# MFX_LEDs.net
KiCad netlist of a schematic drawn in Altium Designer
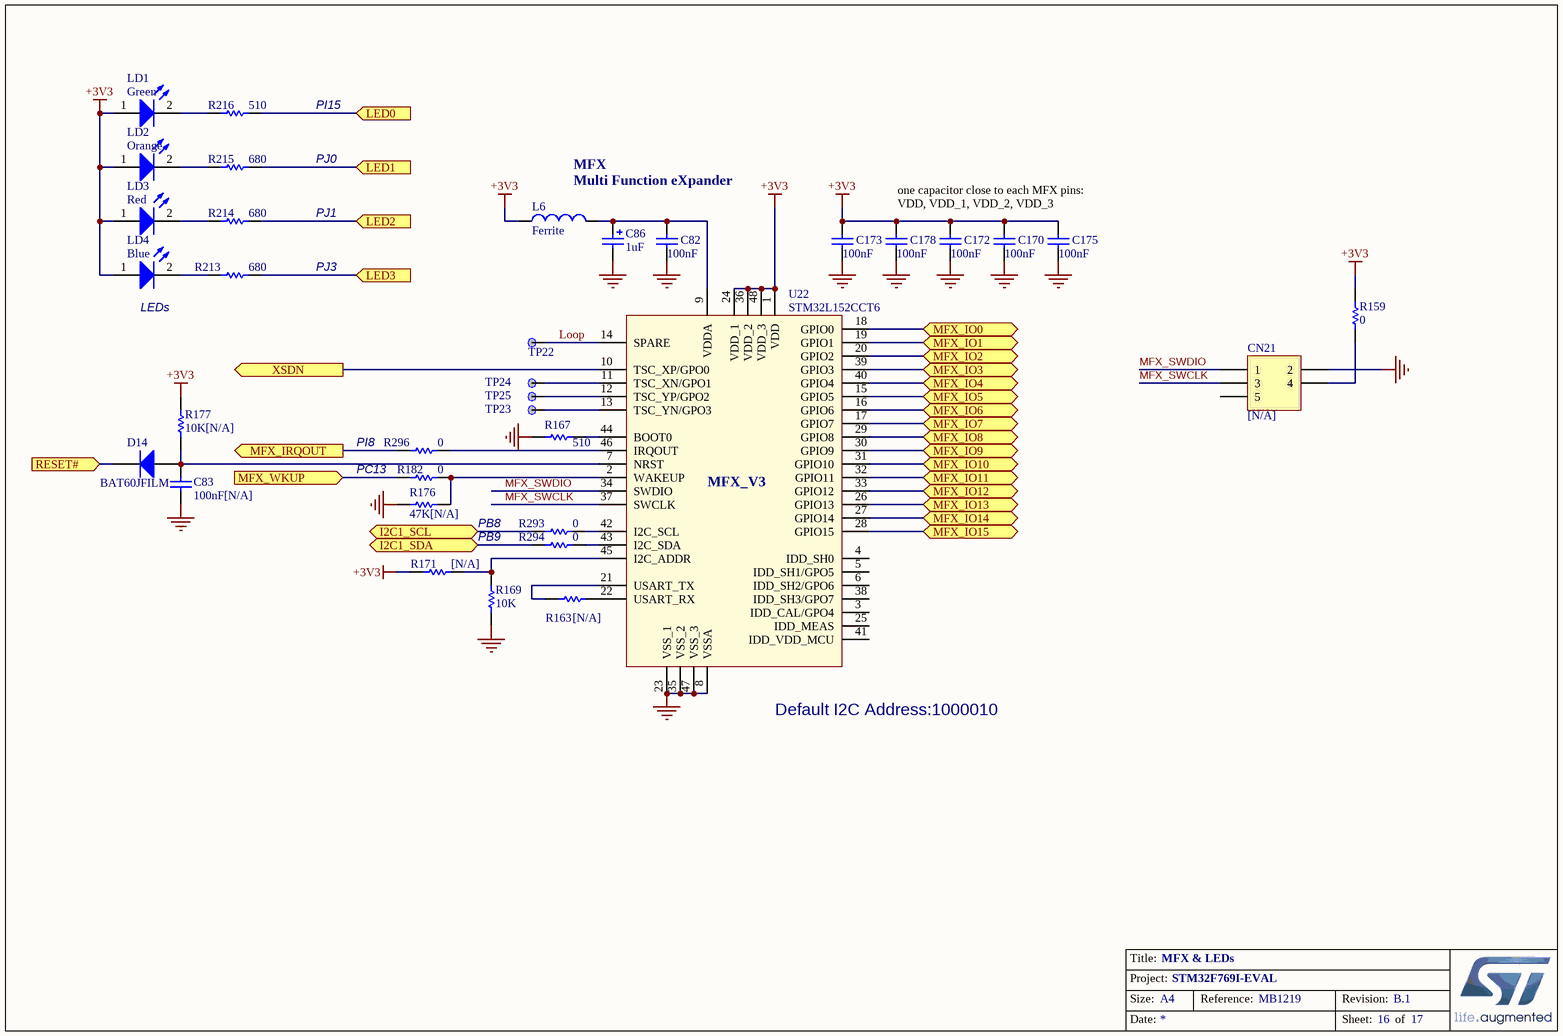
[diagram p0: MFX & LEDs.SchDoc]

(export (version "E")
  (design (tool "Eeschema 10.0.6"))
  (components
    (comp (ref "C82")
      (value "100nF")
      (footprint "0402C")
      (description "Capacitor,100nF,16V,X7R,10%,0402,YAGEO")
      (libsource (lib "MCD_TOOLS") (part "Cap_100nF_X7R_10%_0402"))
    )
    (comp (ref "C83")
      (value "100nF[N/A]")
      (footprint "0402C")
      (description "Capacitor,100nF,16V,X7R,10%,0402,YAGEO")
      (libsource (lib "MCD_TOOLS") (part "Cap_100nF_X7R_10%_0402"))
    )
    (comp (ref "C86")
      (value "1uF")
      (footprint "TAN-A")
      (description "Polarized Capacitor,1uF,16V,10%,typeA,AVX")
      (libsource (lib "MCD_TOOLS") (part "Cap_1uF_POL_10%_TANA"))
    )
    (comp (ref "C170")
      (value "100nF")
      (footprint "0402C")
      (description "Capacitor,100nF,16V,X7R,10%,0402,YAGEO")
      (libsource (lib "MCD_TOOLS") (part "Cap_100nF_X7R_10%_0402"))
    )
    (comp (ref "C172")
      (value "100nF")
      (footprint "0402C")
      (description "Capacitor,100nF,16V,X7R,10%,0402,YAGEO")
      (libsource (lib "MCD_TOOLS") (part "Cap_100nF_X7R_10%_0402"))
    )
    (comp (ref "C173")
      (value "100nF")
      (footprint "0402C")
      (description "Capacitor,100nF,16V,X7R,10%,0402,YAGEO")
      (libsource (lib "MCD_TOOLS") (part "Cap_100nF_X7R_10%_0402"))
    )
    (comp (ref "C175")
      (value "100nF")
      (footprint "0402C")
      (description "Capacitor,100nF,16V,X7R,10%,0402,YAGEO")
      (libsource (lib "MCD_TOOLS") (part "Cap_100nF_X7R_10%_0402"))
    )
    (comp (ref "C178")
      (value "100nF")
      (footprint "0402C")
      (description "Capacitor,100nF,16V,X7R,10%,0402,YAGEO")
      (libsource (lib "MCD_TOOLS") (part "Cap_100nF_X7R_10%_0402"))
    )
    (comp (ref "CN21")
      (value "[N/A]")
      (footprint "HDR_2X3-1_2R54-6")
      (description "Header, 3-Pin, Dual row")
      (fields (field (name "PUBLISHER") "Altium Limited"))
      (libsource (lib "Miscellaneous Connectors") (part "Header 3X2"))
    )
    (comp (ref "D14")
      (value "BAT60JFILM")
      (footprint "SOD-323")
      (description "Default Diode")
      (fields (field (name "PUBLISHER") "Altium Limited"))
      (libsource (lib "Miscellaneous Devices") (part "Diode"))
    )
    (comp (ref "L6")
      (value "Ferrite")
      (footprint "0603L")
      (description "Bead,600R,350mA,0603,FCM1608KF-601T03,Tai-tech")
      (libsource (lib "MCD_TOOLS") (part "BEAD_600R_350MA_0603"))
    )
    (comp (ref "LD1")
      (value "Green")
      (footprint "0603D")
      (description "Typical RED, GREEN, YELLOW, AMBER GaAs LED")
      (fields (field (name "PUBLISHER") "Altium Limited"))
      (libsource (lib "Miscellaneous Devices") (part "LED2"))
    )
    (comp (ref "LD2")
      (value "Orange")
      (footprint "0603D")
      (description "Typical RED, GREEN, YELLOW, AMBER GaAs LED")
      (fields (field (name "PUBLISHER") "Altium Limited"))
      (libsource (lib "Miscellaneous Devices") (part "LED2"))
    )
    (comp (ref "LD3")
      (value "Red")
      (footprint "0603D")
      (description "Typical RED, GREEN, YELLOW, AMBER GaAs LED")
      (fields (field (name "PUBLISHER") "Altium Limited"))
      (libsource (lib "Miscellaneous Devices") (part "LED2"))
    )
    (comp (ref "LD4")
      (value "Blue")
      (footprint "0603D")
      (description "Typical RED, GREEN, YELLOW, AMBER GaAs LED")
      (fields (field (name "PUBLISHER") "Altium Limited"))
      (libsource (lib "Miscellaneous Devices") (part "LED2"))
    )
    (comp (ref "R159")
      (value "0")
      (footprint "0603R")
      (description "Resistor")
      (fields (field (name "PUBLISHER") "Altium Limited"))
      (libsource (lib "Miscellaneous Devices") (part "Res1"))
    )
    (comp (ref "R163")
      (value "[N/A]")
      (footprint "0603R")
      (description "Resistor")
      (fields (field (name "PUBLISHER") "Altium Limited"))
      (libsource (lib "Miscellaneous Devices") (part "res1"))
    )
    (comp (ref "R167")
      (value "510")
      (footprint "0402R")
      (description "Resistor 0402 or 0603 or 0805")
      (libsource (lib "MCD_TOOLS") (part "Resistor_ST"))
    )
    (comp (ref "R169")
      (value "10K")
      (footprint "0402R")
      (description "Resistor 0402 or 0603 or 0805")
      (libsource (lib "MCD_TOOLS") (part "Resistor_ST"))
    )
    (comp (ref "R171")
      (value "[N/A]")
      (footprint "0603R")
      (description "Resistor")
      (fields (field (name "PUBLISHER") "Altium Limited"))
      (libsource (lib "Miscellaneous Devices") (part "Res1"))
    )
    (comp (ref "R176")
      (value "47K[N/A]")
      (footprint "0402R")
      (description "Resistor 0402 or 0603 or 0805")
      (libsource (lib "MCD_TOOLS") (part "Resistor_ST"))
    )
    (comp (ref "R177")
      (value "10K[N/A]")
      (footprint "0402R")
      (description "Resistor 0402 or 0603 or 0805")
      (libsource (lib "MCD_TOOLS") (part "Resistor_ST"))
    )
    (comp (ref "R182")
      (value "0")
      (footprint "0603R")
      (description "Resistor")
      (fields (field (name "PUBLISHER") "Altium Limited"))
      (libsource (lib "Miscellaneous Devices") (part "Res1"))
    )
    (comp (ref "R213")
      (value "680")
      (footprint "0603R")
      (description "Resistor")
      (fields (field (name "PUBLISHER") "Altium Limited"))
      (libsource (lib "Miscellaneous Devices") (part "Res1"))
    )
    (comp (ref "R214")
      (value "680")
      (footprint "0603R")
      (description "Resistor")
      (fields (field (name "PUBLISHER") "Altium Limited"))
      (libsource (lib "Miscellaneous Devices") (part "Res1"))
    )
    (comp (ref "R215")
      (value "680")
      (footprint "0603R")
      (description "Resistor")
      (fields (field (name "PUBLISHER") "Altium Limited"))
      (libsource (lib "Miscellaneous Devices") (part "Res1"))
    )
    (comp (ref "R216")
      (value "510")
      (footprint "0603R")
      (description "Resistor")
      (fields (field (name "PUBLISHER") "Altium Limited"))
      (libsource (lib "Miscellaneous Devices") (part "Res1"))
    )
    (comp (ref "R293")
      (value "0")
      (footprint "0603R")
      (description "Resistor")
      (fields (field (name "PUBLISHER") "Altium Limited"))
      (libsource (lib "Miscellaneous Devices") (part "Res1"))
    )
    (comp (ref "R294")
      (value "0")
      (footprint "0603R")
      (description "Resistor")
      (fields (field (name "PUBLISHER") "Altium Limited"))
      (libsource (lib "Miscellaneous Devices") (part "Res1"))
    )
    (comp (ref "R296")
      (value "0")
      (footprint "0603R")
      (description "Resistor")
      (fields (field (name "PUBLISHER") "Altium Limited"))
      (libsource (lib "Miscellaneous Devices") (part "Res1"))
    )
    (comp (ref "TP22") (value "~") (footprint "TP") (libsource (lib "*") (part "TP")))
    (comp (ref "TP23") (value "~") (footprint "TP") (libsource (lib "*") (part "TP")))
    (comp (ref "TP24") (value "~") (footprint "TP") (libsource (lib "*") (part "TP")))
    (comp (ref "TP25") (value "~") (footprint "TP") (libsource (lib "*") (part "TP")))
    (comp (ref "U22")
      (value "STM32L152CCT6")
      (footprint "LQFP48_0R5_9X9")
      (description "Multifunction expander")
      (libsource (lib "MB1167") (part "MFX"))
    )
  )
  (nets
    (net (code "1") (name "+3V3") (class "Default")
      (node (ref "C170") (pin "2") (pinfunction "2_2") (pintype "passive"))
      (node (ref "C172") (pin "1") (pinfunction "1_1") (pintype "passive"))
      (node (ref "C173") (pin "2") (pinfunction "2_2") (pintype "passive"))
      (node (ref "C175") (pin "2") (pinfunction "2_2") (pintype "passive"))
      (node (ref "C178") (pin "2") (pinfunction "2_2") (pintype "passive"))
      (node (ref "L6") (pin "1") (pinfunction "1_1") (pintype "passive"))
      (node (ref "LD1") (pin "1") (pinfunction "A_1") (pintype "passive"))
      (node (ref "LD2") (pin "1") (pinfunction "A_1") (pintype "passive"))
      (node (ref "LD3") (pin "1") (pinfunction "A_1") (pintype "passive"))
      (node (ref "LD4") (pin "1") (pinfunction "A_1") (pintype "passive"))
      (node (ref "R159") (pin "1") (pinfunction "1_1") (pintype "passive"))
      (node (ref "R171") (pin "2") (pinfunction "2_2") (pintype "passive"))
      (node (ref "R177") (pin "2") (pinfunction "2_2") (pintype "passive"))
      (node (ref "U22") (pin "1") (pinfunction "VDD_1") (pintype "passive"))
      (node (ref "U22") (pin "24") (pinfunction "VDD_1_24") (pintype "passive"))
      (node (ref "U22") (pin "36") (pinfunction "VDD_2_36") (pintype "passive"))
      (node (ref "U22") (pin "48") (pinfunction "VDD_3_48") (pintype "passive"))
    )
    (net (code "2") (name "/I2C1_SCL") (class "Default")
      (node (ref "R293") (pin "1") (pinfunction "1_1") (pintype "passive"))
    )
    (net (code "3") (name "/I2C1_SDA") (class "Default")
      (node (ref "R294") (pin "1") (pinfunction "1_1") (pintype "passive"))
    )
    (net (code "4") (name "/LED0") (class "Default")
      (node (ref "R216") (pin "1") (pinfunction "1_1") (pintype "passive"))
    )
    (net (code "5") (name "/LED1") (class "Default")
      (node (ref "R215") (pin "1") (pinfunction "1_1") (pintype "passive"))
    )
    (net (code "6") (name "/LED2") (class "Default")
      (node (ref "R214") (pin "1") (pinfunction "1_1") (pintype "passive"))
    )
    (net (code "7") (name "/LED3") (class "Default")
      (node (ref "R213") (pin "1") (pinfunction "1_1") (pintype "passive"))
    )
    (net (code "8") (name "/Loop") (class "Default")
      (node (ref "TP22") (pin "1") (pinfunction "1_1") (pintype "passive"))
      (node (ref "U22") (pin "14") (pinfunction "SPARE_14") (pintype "passive"))
    )
    (net (code "9") (name "/MFX_IO0") (class "Default")
      (node (ref "U22") (pin "18") (pinfunction "GPIO0_18") (pintype "passive"))
    )
    (net (code "10") (name "/MFX_IO1") (class "Default")
      (node (ref "U22") (pin "19") (pinfunction "GPIO1_19") (pintype "passive"))
    )
    (net (code "11") (name "/MFX_IO2") (class "Default")
      (node (ref "U22") (pin "20") (pinfunction "GPIO2_20") (pintype "passive"))
    )
    (net (code "12") (name "/MFX_IO3") (class "Default")
      (node (ref "U22") (pin "39") (pinfunction "GPIO3_39") (pintype "passive"))
    )
    (net (code "13") (name "/MFX_IO4") (class "Default")
      (node (ref "U22") (pin "40") (pinfunction "GPIO4_40") (pintype "passive"))
    )
    (net (code "14") (name "/MFX_IO5") (class "Default")
      (node (ref "U22") (pin "15") (pinfunction "GPIO5_15") (pintype "passive"))
    )
    (net (code "15") (name "/MFX_IO6") (class "Default")
      (node (ref "U22") (pin "16") (pinfunction "GPIO6_16") (pintype "passive"))
    )
    (net (code "16") (name "/MFX_IO7") (class "Default")
      (node (ref "U22") (pin "17") (pinfunction "GPIO7_17") (pintype "passive"))
    )
    (net (code "17") (name "/MFX_IO8") (class "Default")
      (node (ref "U22") (pin "29") (pinfunction "GPIO8_29") (pintype "passive"))
    )
    (net (code "18") (name "/MFX_IO9") (class "Default")
      (node (ref "U22") (pin "30") (pinfunction "GPIO9_30") (pintype "passive"))
    )
    (net (code "19") (name "/MFX_IO10") (class "Default")
      (node (ref "U22") (pin "31") (pinfunction "GPIO10_31") (pintype "passive"))
    )
    (net (code "20") (name "/MFX_IO11") (class "Default")
      (node (ref "U22") (pin "32") (pinfunction "GPIO11_32") (pintype "passive"))
    )
    (net (code "21") (name "/MFX_IO12") (class "Default")
      (node (ref "U22") (pin "33") (pinfunction "GPIO12_33") (pintype "passive"))
    )
    (net (code "22") (name "/MFX_IO13") (class "Default")
      (node (ref "U22") (pin "26") (pinfunction "GPIO13_26") (pintype "passive"))
    )
    (net (code "23") (name "/MFX_IO14") (class "Default")
      (node (ref "U22") (pin "27") (pinfunction "GPIO14_27") (pintype "passive"))
    )
    (net (code "24") (name "/MFX_IO15") (class "Default")
      (node (ref "U22") (pin "28") (pinfunction "GPIO15_28") (pintype "passive"))
    )
    (net (code "25") (name "/MFX_IRQOUT") (class "Default")
      (node (ref "R296") (pin "1") (pinfunction "1_1") (pintype "passive"))
    )
    (net (code "26") (name "/MFX_SWCLK") (class "Default")
      (node (ref "CN21") (pin "3") (pinfunction "3_3") (pintype "passive"))
      (node (ref "U22") (pin "37") (pinfunction "SWCLK_37") (pintype "passive"))
    )
    (net (code "27") (name "/MFX_SWDIO") (class "Default")
      (node (ref "CN21") (pin "1") (pinfunction "1_1") (pintype "passive"))
      (node (ref "U22") (pin "34") (pinfunction "SWDIO_34") (pintype "passive"))
    )
    (net (code "28") (name "/MFX_WKUP") (class "Default")
      (node (ref "R182") (pin "2") (pinfunction "2_2") (pintype "passive"))
    )
    (net (code "29") (name "/RESET#") (class "Default")
      (node (ref "D14") (pin "2") (pinfunction "K_2") (pintype "passive"))
    )
    (net (code "30") (name "/XSDN") (class "Default")
      (node (ref "U22") (pin "10") (pinfunction "TSC_XP/GPO0_10") (pintype "passive"))
    )
    (net (code "31") (name "GND") (class "Default")
      (node (ref "C170") (pin "1") (pinfunction "1_1") (pintype "passive"))
      (node (ref "C172") (pin "2") (pinfunction "2_2") (pintype "passive"))
      (node (ref "C173") (pin "1") (pinfunction "1_1") (pintype "passive"))
      (node (ref "C175") (pin "1") (pinfunction "1_1") (pintype "passive"))
      (node (ref "C178") (pin "1") (pinfunction "1_1") (pintype "passive"))
      (node (ref "C82") (pin "1") (pinfunction "1_1") (pintype "passive"))
      (node (ref "C83") (pin "1") (pinfunction "1_1") (pintype "passive"))
      (node (ref "C86") (pin "2") (pinfunction "2_2") (pintype "passive"))
      (node (ref "CN21") (pin "2") (pinfunction "2_2") (pintype "passive"))
      (node (ref "R167") (pin "2") (pinfunction "2_2") (pintype "passive"))
      (node (ref "R169") (pin "2") (pinfunction "2_2") (pintype "passive"))
      (node (ref "R176") (pin "1") (pinfunction "1_1") (pintype "passive"))
      (node (ref "U22") (pin "23") (pinfunction "VSS_1_23") (pintype "passive"))
      (node (ref "U22") (pin "35") (pinfunction "VSS_2_35") (pintype "passive"))
      (node (ref "U22") (pin "47") (pinfunction "VSS_3_47") (pintype "passive"))
      (node (ref "U22") (pin "8") (pinfunction "VSSA_8") (pintype "passive"))
    )
    (net (code "32") (name "Net-(CN21-Pad4)") (class "Default")
      (node (ref "CN21") (pin "4") (pinfunction "4_4") (pintype "passive"))
      (node (ref "R159") (pin "2") (pinfunction "2_2") (pintype "passive"))
    )
    (net (code "33") (name "Net-(D14-A)") (class "Default")
      (node (ref "C83") (pin "2") (pinfunction "2_2") (pintype "passive"))
      (node (ref "D14") (pin "1") (pinfunction "A_1") (pintype "passive"))
      (node (ref "R177") (pin "1") (pinfunction "1_1") (pintype "passive"))
      (node (ref "U22") (pin "7") (pinfunction "NRST_7") (pintype "passive"))
    )
    (net (code "34") (name "Net-(LD1-K)") (class "Default")
      (node (ref "LD1") (pin "2") (pinfunction "K_2") (pintype "passive"))
      (node (ref "R216") (pin "2") (pinfunction "2_2") (pintype "passive"))
    )
    (net (code "35") (name "Net-(LD2-K)") (class "Default")
      (node (ref "LD2") (pin "2") (pinfunction "K_2") (pintype "passive"))
      (node (ref "R215") (pin "2") (pinfunction "2_2") (pintype "passive"))
    )
    (net (code "36") (name "Net-(LD3-K)") (class "Default")
      (node (ref "LD3") (pin "2") (pinfunction "K_2") (pintype "passive"))
      (node (ref "R214") (pin "2") (pinfunction "2_2") (pintype "passive"))
    )
    (net (code "37") (name "Net-(LD4-K)") (class "Default")
      (node (ref "LD4") (pin "2") (pinfunction "K_2") (pintype "passive"))
      (node (ref "R213") (pin "2") (pinfunction "2_2") (pintype "passive"))
    )
    (net (code "38") (name "Net-(U22-BOOT0)") (class "Default")
      (node (ref "R167") (pin "1") (pinfunction "1_1") (pintype "passive"))
      (node (ref "U22") (pin "44") (pinfunction "BOOT0_44") (pintype "passive"))
    )
    (net (code "39") (name "Net-(U22-I2C_ADDR)") (class "Default")
      (node (ref "R169") (pin "1") (pinfunction "1_1") (pintype "passive"))
      (node (ref "R171") (pin "1") (pinfunction "1_1") (pintype "passive"))
      (node (ref "U22") (pin "45") (pinfunction "I2C_ADDR_45") (pintype "passive"))
    )
    (net (code "40") (name "Net-(U22-I2C_SCL)") (class "Default")
      (node (ref "R293") (pin "2") (pinfunction "2_2") (pintype "passive"))
      (node (ref "U22") (pin "42") (pinfunction "I2C_SCL_42") (pintype "passive"))
    )
    (net (code "41") (name "Net-(U22-I2C_SDA)") (class "Default")
      (node (ref "R294") (pin "2") (pinfunction "2_2") (pintype "passive"))
      (node (ref "U22") (pin "43") (pinfunction "I2C_SDA_43") (pintype "passive"))
    )
    (net (code "42") (name "Net-(U22-IRQOUT)") (class "Default")
      (node (ref "R296") (pin "2") (pinfunction "2_2") (pintype "passive"))
      (node (ref "U22") (pin "46") (pinfunction "IRQOUT_46") (pintype "passive"))
    )
    (net (code "43") (name "Net-(U22-TSC_XN{slash}GPO1)") (class "Default")
      (node (ref "TP24") (pin "1") (pinfunction "1_1") (pintype "passive"))
      (node (ref "U22") (pin "11") (pinfunction "TSC_XN/GPO1_11") (pintype "passive"))
    )
    (net (code "44") (name "Net-(U22-TSC_YN{slash}GPO3)") (class "Default")
      (node (ref "TP23") (pin "1") (pinfunction "1_1") (pintype "passive"))
      (node (ref "U22") (pin "13") (pinfunction "TSC_YN/GPO3_13") (pintype "passive"))
    )
    (net (code "45") (name "Net-(U22-TSC_YP{slash}GPO2)") (class "Default")
      (node (ref "TP25") (pin "1") (pinfunction "1_1") (pintype "passive"))
      (node (ref "U22") (pin "12") (pinfunction "TSC_YP/GPO2_12") (pintype "passive"))
    )
    (net (code "46") (name "Net-(U22-USART_RX)") (class "Default")
      (node (ref "R163") (pin "2") (pinfunction "2_2") (pintype "passive"))
      (node (ref "U22") (pin "22") (pinfunction "USART_RX_22") (pintype "passive"))
    )
    (net (code "47") (name "Net-(U22-USART_TX)") (class "Default")
      (node (ref "R163") (pin "1") (pinfunction "1_1") (pintype "passive"))
      (node (ref "U22") (pin "21") (pinfunction "USART_TX_21") (pintype "passive"))
    )
    (net (code "48") (name "Net-(U22-VDDA)") (class "Default")
      (node (ref "C82") (pin "2") (pinfunction "2_2") (pintype "passive"))
      (node (ref "C86") (pin "1") (pinfunction "1_1") (pintype "passive"))
      (node (ref "L6") (pin "2") (pinfunction "2_2") (pintype "passive"))
      (node (ref "U22") (pin "9") (pinfunction "VDDA_9") (pintype "passive"))
    )
    (net (code "49") (name "Net-(U22-WAKEUP)") (class "Default")
      (node (ref "R176") (pin "2") (pinfunction "2_2") (pintype "passive"))
      (node (ref "R182") (pin "1") (pinfunction "1_1") (pintype "passive"))
      (node (ref "U22") (pin "2") (pinfunction "WAKEUP_2") (pintype "passive"))
    )
    (net (code "50") (name "unconnected-(CN21-Pad5)") (class "Default")
      (node (ref "CN21") (pin "5") (pinfunction "5_5") (pintype "passive"))
    )
    (net (code "51") (name "unconnected-(U22-IDD_CAL{slash}GPO4-Pad3)") (class "Default")
      (node (ref "U22") (pin "3") (pinfunction "IDD_CAL/GPO4_3") (pintype "passive"))
    )
    (net (code "52") (name "unconnected-(U22-IDD_MEAS-Pad25)") (class "Default")
      (node (ref "U22") (pin "25") (pinfunction "IDD_MEAS_25") (pintype "passive"))
    )
    (net (code "53") (name "unconnected-(U22-IDD_SH0-Pad4)") (class "Default")
      (node (ref "U22") (pin "4") (pinfunction "IDD_SH0_4") (pintype "passive"))
    )
    (net (code "54") (name "unconnected-(U22-IDD_SH1{slash}GPO5-Pad5)") (class "Default")
      (node (ref "U22") (pin "5") (pinfunction "IDD_SH1/GPO5_5") (pintype "passive"))
    )
    (net (code "55") (name "unconnected-(U22-IDD_SH2{slash}GPO6-Pad6)") (class "Default")
      (node (ref "U22") (pin "6") (pinfunction "IDD_SH2/GPO6_6") (pintype "passive"))
    )
    (net (code "56") (name "unconnected-(U22-IDD_SH3{slash}GPO7-Pad38)") (class "Default")
      (node (ref "U22") (pin "38") (pinfunction "IDD_SH3/GPO7_38") (pintype "passive"))
    )
    (net (code "57") (name "unconnected-(U22-IDD_VDD_MCU-Pad41)") (class "Default")
      (node (ref "U22") (pin "41") (pinfunction "IDD_VDD_MCU_41") (pintype "passive"))
    )
  )
)
